# SparkFun_ProtoShield_Kit_rev40.net
KiCad netlist of a schematic drawn in EAGLE
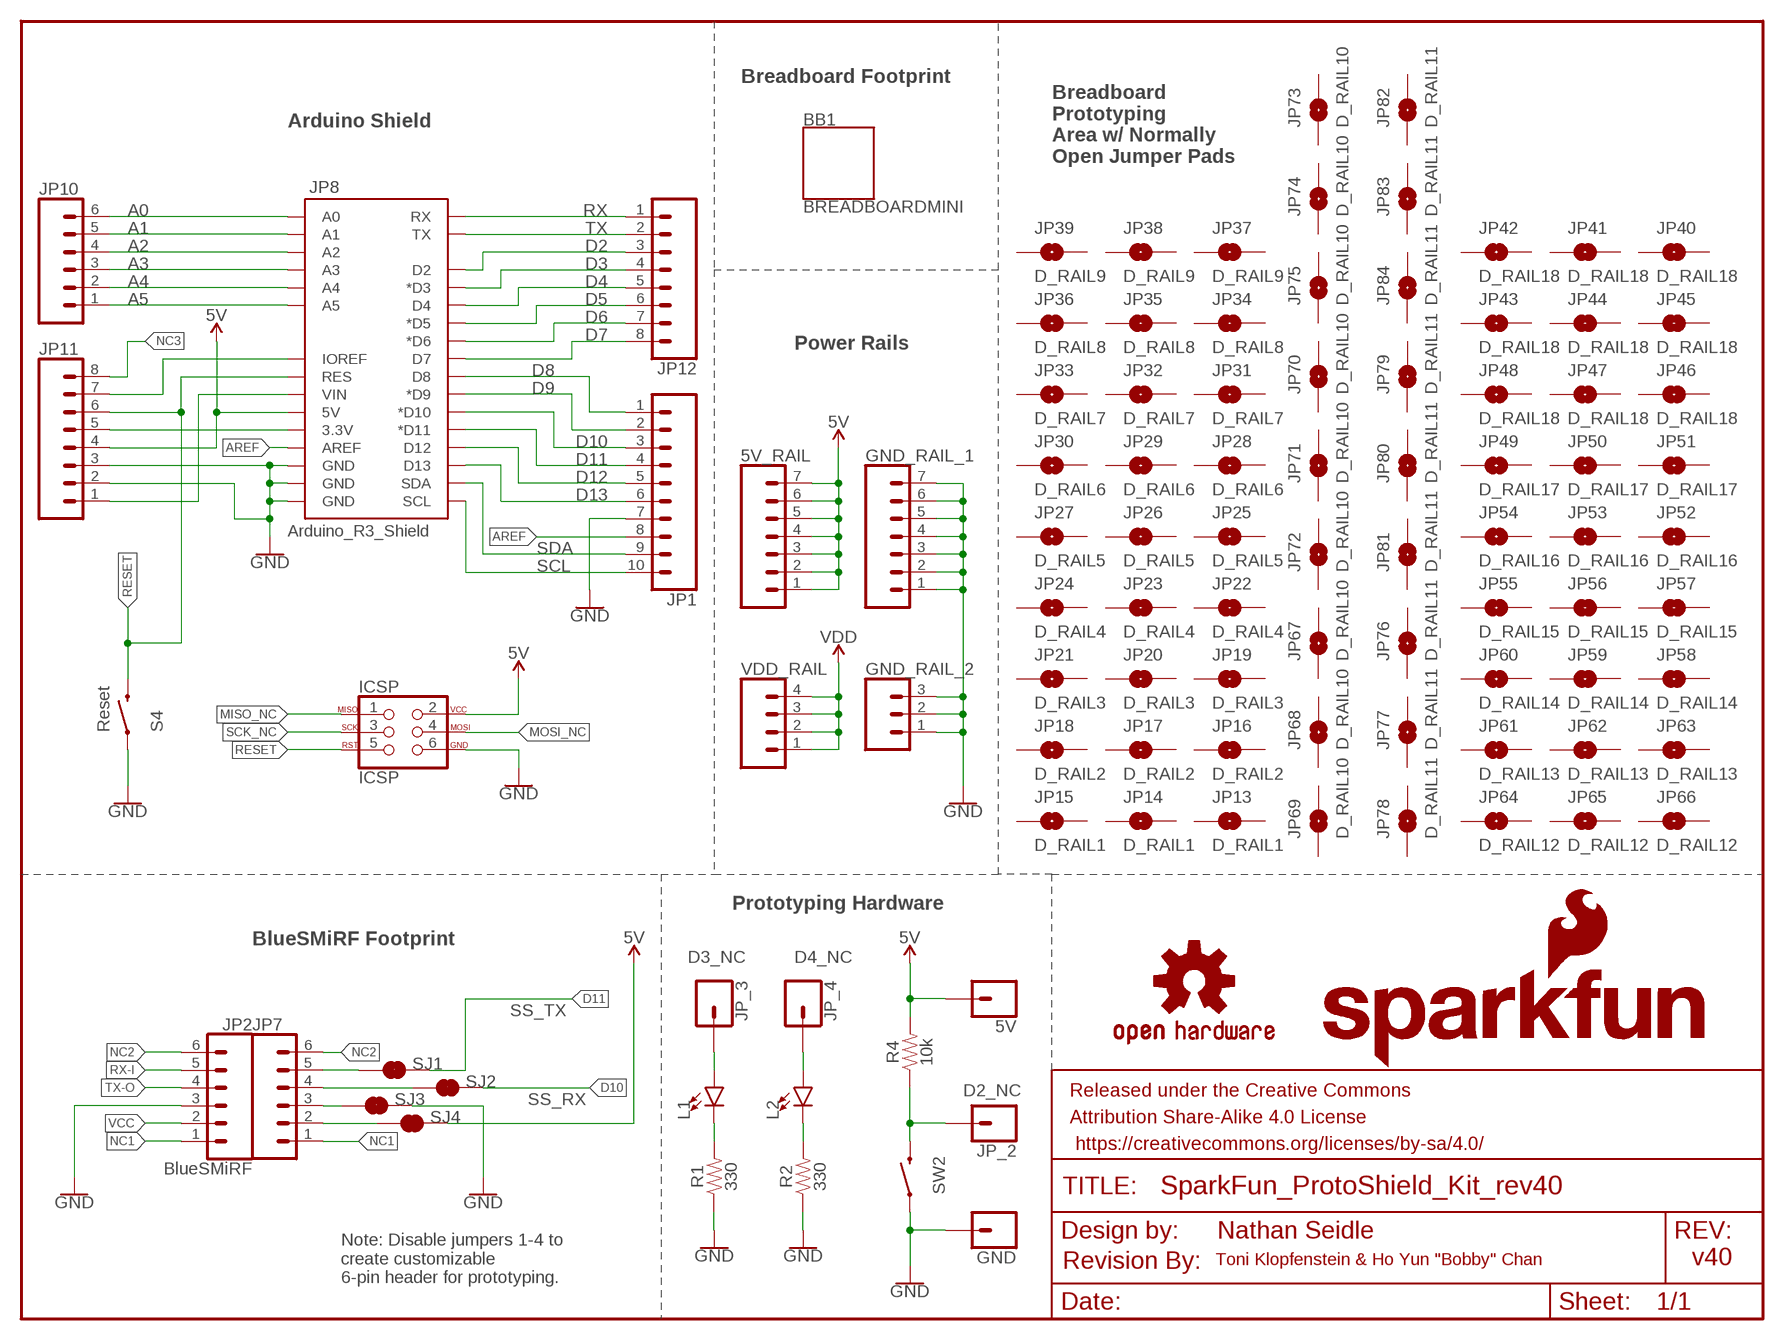
[diagram p0: schematic, sheet 1]

(export (version "E")
  (design (tool "Eeschema 10.0.6"))
  (components
    (comp (ref "5V")
      (value "CONN_01")
      (footprint "eagle-import:1X01")
      (libsource (lib "eagle-import") (part "CONN_01"))
    )
    (comp (ref "5V_RAIL")
      (value "CONN_07NO_SILK")
      (footprint "eagle-import:1X07_NO_SILK")
      (libsource (lib "eagle-import") (part "CONN_07NO_SILK"))
    )
    (comp (ref "BB1")
      (value "BREADBOARDMINI")
      (footprint "eagle-import:BREADBOARD-MINI")
      (libsource (lib "eagle-import") (part "BREADBOARDMINI"))
    )
    (comp (ref "FRAME1")
      (value "FRAME-LETTER")
      (footprint "eagle-import:CREATIVE_COMMONS")
      (libsource (lib "eagle-import") (part "FRAME-LETTER"))
    )
    (comp (ref "GND")
      (value "CONN_01")
      (footprint "eagle-import:1X01")
      (libsource (lib "eagle-import") (part "CONN_01"))
    )
    (comp (ref "GND_RAIL_1")
      (value "CONN_07NO_SILK")
      (footprint "eagle-import:1X07_NO_SILK")
      (libsource (lib "eagle-import") (part "CONN_07NO_SILK"))
    )
    (comp (ref "GND_RAIL_2")
      (value "CONN_031X03_NO_SILK")
      (footprint "eagle-import:1X03_NO_SILK")
      (libsource (lib "eagle-import") (part "CONN_031X03_NO_SILK"))
    )
    (comp (ref "ICSP")
      (value "ICSP")
      (footprint "eagle-import:2X3")
      (libsource (lib "eagle-import") (part "AVR_SPI_PROG_3X2PTH"))
    )
    (comp (ref "JP1")
      (value "CONN_10\"")
      (footprint "eagle-import:1X10")
      (libsource (lib "eagle-import") (part "CONN_10{dblquote}"))
    )
    (comp (ref "JP2")
      (value "BlueSMiRF")
      (footprint "eagle-import:1X06")
      (libsource (lib "eagle-import") (part "CONN_06SILK_FEMALE_PTH"))
    )
    (comp (ref "JP7")
      (value "CONN_06SILK_FEMALE_PTH")
      (footprint "eagle-import:1X06")
      (libsource (lib "eagle-import") (part "CONN_06SILK_FEMALE_PTH"))
    )
    (comp (ref "JP8")
      (value "ARDUINO_R3_SHIELDR3_PROTO_SHIELD")
      (footprint "eagle-import:UNO_R3_PROTO_SHIELD")
      (libsource (lib "eagle-import") (part "ARDUINO_R3_SHIELDR3_PROTO_SHIELD"))
    )
    (comp (ref "JP10")
      (value "CONN_06SILK_FEMALE_PTH")
      (footprint "eagle-import:1X06")
      (libsource (lib "eagle-import") (part "CONN_06SILK_FEMALE_PTH"))
    )
    (comp (ref "JP11")
      (value "CONN_08\"")
      (footprint "eagle-import:1X08")
      (libsource (lib "eagle-import") (part "CONN_08{dblquote}"))
    )
    (comp (ref "JP12")
      (value "CONN_08\"")
      (footprint "eagle-import:1X08")
      (libsource (lib "eagle-import") (part "CONN_08{dblquote}"))
    )
    (comp (ref "JP13")
      (value "D_RAIL1")
      (footprint "eagle-import:SMT-JUMPER_2_NO_NO-SILK")
      (libsource (lib "eagle-import") (part "JUMPER-SMT_2_NO_NO-SILK"))
    )
    (comp (ref "JP14")
      (value "D_RAIL1")
      (footprint "eagle-import:SMT-JUMPER_2_NO_NO-SILK")
      (libsource (lib "eagle-import") (part "JUMPER-SMT_2_NO_NO-SILK"))
    )
    (comp (ref "JP15")
      (value "D_RAIL1")
      (footprint "eagle-import:SMT-JUMPER_2_NO_NO-SILK")
      (libsource (lib "eagle-import") (part "JUMPER-SMT_2_NO_NO-SILK"))
    )
    (comp (ref "JP16")
      (value "D_RAIL2")
      (footprint "eagle-import:SMT-JUMPER_2_NO_NO-SILK")
      (libsource (lib "eagle-import") (part "JUMPER-SMT_2_NO_NO-SILK"))
    )
    (comp (ref "JP17")
      (value "D_RAIL2")
      (footprint "eagle-import:SMT-JUMPER_2_NO_NO-SILK")
      (libsource (lib "eagle-import") (part "JUMPER-SMT_2_NO_NO-SILK"))
    )
    (comp (ref "JP18")
      (value "D_RAIL2")
      (footprint "eagle-import:SMT-JUMPER_2_NO_NO-SILK")
      (libsource (lib "eagle-import") (part "JUMPER-SMT_2_NO_NO-SILK"))
    )
    (comp (ref "JP19")
      (value "D_RAIL3")
      (footprint "eagle-import:SMT-JUMPER_2_NO_NO-SILK")
      (libsource (lib "eagle-import") (part "JUMPER-SMT_2_NO_NO-SILK"))
    )
    (comp (ref "JP20")
      (value "D_RAIL3")
      (footprint "eagle-import:SMT-JUMPER_2_NO_NO-SILK")
      (libsource (lib "eagle-import") (part "JUMPER-SMT_2_NO_NO-SILK"))
    )
    (comp (ref "JP21")
      (value "D_RAIL3")
      (footprint "eagle-import:SMT-JUMPER_2_NO_NO-SILK")
      (libsource (lib "eagle-import") (part "JUMPER-SMT_2_NO_NO-SILK"))
    )
    (comp (ref "JP22")
      (value "D_RAIL4")
      (footprint "eagle-import:SMT-JUMPER_2_NO_NO-SILK")
      (libsource (lib "eagle-import") (part "JUMPER-SMT_2_NO_NO-SILK"))
    )
    (comp (ref "JP23")
      (value "D_RAIL4")
      (footprint "eagle-import:SMT-JUMPER_2_NO_NO-SILK")
      (libsource (lib "eagle-import") (part "JUMPER-SMT_2_NO_NO-SILK"))
    )
    (comp (ref "JP24")
      (value "D_RAIL4")
      (footprint "eagle-import:SMT-JUMPER_2_NO_NO-SILK")
      (libsource (lib "eagle-import") (part "JUMPER-SMT_2_NO_NO-SILK"))
    )
    (comp (ref "JP25")
      (value "D_RAIL5")
      (footprint "eagle-import:SMT-JUMPER_2_NO_NO-SILK")
      (libsource (lib "eagle-import") (part "JUMPER-SMT_2_NO_NO-SILK"))
    )
    (comp (ref "JP26")
      (value "D_RAIL5")
      (footprint "eagle-import:SMT-JUMPER_2_NO_NO-SILK")
      (libsource (lib "eagle-import") (part "JUMPER-SMT_2_NO_NO-SILK"))
    )
    (comp (ref "JP27")
      (value "D_RAIL5")
      (footprint "eagle-import:SMT-JUMPER_2_NO_NO-SILK")
      (libsource (lib "eagle-import") (part "JUMPER-SMT_2_NO_NO-SILK"))
    )
    (comp (ref "JP28")
      (value "D_RAIL6")
      (footprint "eagle-import:SMT-JUMPER_2_NO_NO-SILK")
      (libsource (lib "eagle-import") (part "JUMPER-SMT_2_NO_NO-SILK"))
    )
    (comp (ref "JP29")
      (value "D_RAIL6")
      (footprint "eagle-import:SMT-JUMPER_2_NO_NO-SILK")
      (libsource (lib "eagle-import") (part "JUMPER-SMT_2_NO_NO-SILK"))
    )
    (comp (ref "JP30")
      (value "D_RAIL6")
      (footprint "eagle-import:SMT-JUMPER_2_NO_NO-SILK")
      (libsource (lib "eagle-import") (part "JUMPER-SMT_2_NO_NO-SILK"))
    )
    (comp (ref "JP31")
      (value "D_RAIL7")
      (footprint "eagle-import:SMT-JUMPER_2_NO_NO-SILK")
      (libsource (lib "eagle-import") (part "JUMPER-SMT_2_NO_NO-SILK"))
    )
    (comp (ref "JP32")
      (value "D_RAIL7")
      (footprint "eagle-import:SMT-JUMPER_2_NO_NO-SILK")
      (libsource (lib "eagle-import") (part "JUMPER-SMT_2_NO_NO-SILK"))
    )
    (comp (ref "JP33")
      (value "D_RAIL7")
      (footprint "eagle-import:SMT-JUMPER_2_NO_NO-SILK")
      (libsource (lib "eagle-import") (part "JUMPER-SMT_2_NO_NO-SILK"))
    )
    (comp (ref "JP34")
      (value "D_RAIL8")
      (footprint "eagle-import:SMT-JUMPER_2_NO_NO-SILK")
      (libsource (lib "eagle-import") (part "JUMPER-SMT_2_NO_NO-SILK"))
    )
    (comp (ref "JP35")
      (value "D_RAIL8")
      (footprint "eagle-import:SMT-JUMPER_2_NO_NO-SILK")
      (libsource (lib "eagle-import") (part "JUMPER-SMT_2_NO_NO-SILK"))
    )
    (comp (ref "JP36")
      (value "D_RAIL8")
      (footprint "eagle-import:SMT-JUMPER_2_NO_NO-SILK")
      (libsource (lib "eagle-import") (part "JUMPER-SMT_2_NO_NO-SILK"))
    )
    (comp (ref "JP37")
      (value "D_RAIL9")
      (footprint "eagle-import:SMT-JUMPER_2_NO_NO-SILK")
      (libsource (lib "eagle-import") (part "JUMPER-SMT_2_NO_NO-SILK"))
    )
    (comp (ref "JP38")
      (value "D_RAIL9")
      (footprint "eagle-import:SMT-JUMPER_2_NO_NO-SILK")
      (libsource (lib "eagle-import") (part "JUMPER-SMT_2_NO_NO-SILK"))
    )
    (comp (ref "JP39")
      (value "D_RAIL9")
      (footprint "eagle-import:SMT-JUMPER_2_NO_NO-SILK")
      (libsource (lib "eagle-import") (part "JUMPER-SMT_2_NO_NO-SILK"))
    )
    (comp (ref "JP40")
      (value "D_RAIL18")
      (footprint "eagle-import:SMT-JUMPER_2_NO_NO-SILK")
      (libsource (lib "eagle-import") (part "JUMPER-SMT_2_NO_NO-SILK"))
    )
    (comp (ref "JP41")
      (value "D_RAIL18")
      (footprint "eagle-import:SMT-JUMPER_2_NO_NO-SILK")
      (libsource (lib "eagle-import") (part "JUMPER-SMT_2_NO_NO-SILK"))
    )
    (comp (ref "JP42")
      (value "D_RAIL18")
      (footprint "eagle-import:SMT-JUMPER_2_NO_NO-SILK")
      (libsource (lib "eagle-import") (part "JUMPER-SMT_2_NO_NO-SILK"))
    )
    (comp (ref "JP43")
      (value "D_RAIL18")
      (footprint "eagle-import:SMT-JUMPER_2_NO_NO-SILK")
      (libsource (lib "eagle-import") (part "JUMPER-SMT_2_NO_NO-SILK"))
    )
    (comp (ref "JP44")
      (value "D_RAIL18")
      (footprint "eagle-import:SMT-JUMPER_2_NO_NO-SILK")
      (libsource (lib "eagle-import") (part "JUMPER-SMT_2_NO_NO-SILK"))
    )
    (comp (ref "JP45")
      (value "D_RAIL18")
      (footprint "eagle-import:SMT-JUMPER_2_NO_NO-SILK")
      (libsource (lib "eagle-import") (part "JUMPER-SMT_2_NO_NO-SILK"))
    )
    (comp (ref "JP46")
      (value "D_RAIL18")
      (footprint "eagle-import:SMT-JUMPER_2_NO_NO-SILK")
      (libsource (lib "eagle-import") (part "JUMPER-SMT_2_NO_NO-SILK"))
    )
    (comp (ref "JP47")
      (value "D_RAIL18")
      (footprint "eagle-import:SMT-JUMPER_2_NO_NO-SILK")
      (libsource (lib "eagle-import") (part "JUMPER-SMT_2_NO_NO-SILK"))
    )
    (comp (ref "JP48")
      (value "D_RAIL18")
      (footprint "eagle-import:SMT-JUMPER_2_NO_NO-SILK")
      (libsource (lib "eagle-import") (part "JUMPER-SMT_2_NO_NO-SILK"))
    )
    (comp (ref "JP49")
      (value "D_RAIL17")
      (footprint "eagle-import:SMT-JUMPER_2_NO_NO-SILK")
      (libsource (lib "eagle-import") (part "JUMPER-SMT_2_NO_NO-SILK"))
    )
    (comp (ref "JP50")
      (value "D_RAIL17")
      (footprint "eagle-import:SMT-JUMPER_2_NO_NO-SILK")
      (libsource (lib "eagle-import") (part "JUMPER-SMT_2_NO_NO-SILK"))
    )
    (comp (ref "JP51")
      (value "D_RAIL17")
      (footprint "eagle-import:SMT-JUMPER_2_NO_NO-SILK")
      (libsource (lib "eagle-import") (part "JUMPER-SMT_2_NO_NO-SILK"))
    )
    (comp (ref "JP52")
      (value "D_RAIL16")
      (footprint "eagle-import:SMT-JUMPER_2_NO_NO-SILK")
      (libsource (lib "eagle-import") (part "JUMPER-SMT_2_NO_NO-SILK"))
    )
    (comp (ref "JP53")
      (value "D_RAIL16")
      (footprint "eagle-import:SMT-JUMPER_2_NO_NO-SILK")
      (libsource (lib "eagle-import") (part "JUMPER-SMT_2_NO_NO-SILK"))
    )
    (comp (ref "JP54")
      (value "D_RAIL16")
      (footprint "eagle-import:SMT-JUMPER_2_NO_NO-SILK")
      (libsource (lib "eagle-import") (part "JUMPER-SMT_2_NO_NO-SILK"))
    )
    (comp (ref "JP55")
      (value "D_RAIL15")
      (footprint "eagle-import:SMT-JUMPER_2_NO_NO-SILK")
      (libsource (lib "eagle-import") (part "JUMPER-SMT_2_NO_NO-SILK"))
    )
    (comp (ref "JP56")
      (value "D_RAIL15")
      (footprint "eagle-import:SMT-JUMPER_2_NO_NO-SILK")
      (libsource (lib "eagle-import") (part "JUMPER-SMT_2_NO_NO-SILK"))
    )
    (comp (ref "JP57")
      (value "D_RAIL15")
      (footprint "eagle-import:SMT-JUMPER_2_NO_NO-SILK")
      (libsource (lib "eagle-import") (part "JUMPER-SMT_2_NO_NO-SILK"))
    )
    (comp (ref "JP58")
      (value "D_RAIL14")
      (footprint "eagle-import:SMT-JUMPER_2_NO_NO-SILK")
      (libsource (lib "eagle-import") (part "JUMPER-SMT_2_NO_NO-SILK"))
    )
    (comp (ref "JP59")
      (value "D_RAIL14")
      (footprint "eagle-import:SMT-JUMPER_2_NO_NO-SILK")
      (libsource (lib "eagle-import") (part "JUMPER-SMT_2_NO_NO-SILK"))
    )
    (comp (ref "JP60")
      (value "D_RAIL14")
      (footprint "eagle-import:SMT-JUMPER_2_NO_NO-SILK")
      (libsource (lib "eagle-import") (part "JUMPER-SMT_2_NO_NO-SILK"))
    )
    (comp (ref "JP61")
      (value "D_RAIL13")
      (footprint "eagle-import:SMT-JUMPER_2_NO_NO-SILK")
      (libsource (lib "eagle-import") (part "JUMPER-SMT_2_NO_NO-SILK"))
    )
    (comp (ref "JP62")
      (value "D_RAIL13")
      (footprint "eagle-import:SMT-JUMPER_2_NO_NO-SILK")
      (libsource (lib "eagle-import") (part "JUMPER-SMT_2_NO_NO-SILK"))
    )
    (comp (ref "JP63")
      (value "D_RAIL13")
      (footprint "eagle-import:SMT-JUMPER_2_NO_NO-SILK")
      (libsource (lib "eagle-import") (part "JUMPER-SMT_2_NO_NO-SILK"))
    )
    (comp (ref "JP64")
      (value "D_RAIL12")
      (footprint "eagle-import:SMT-JUMPER_2_NO_NO-SILK")
      (libsource (lib "eagle-import") (part "JUMPER-SMT_2_NO_NO-SILK"))
    )
    (comp (ref "JP65")
      (value "D_RAIL12")
      (footprint "eagle-import:SMT-JUMPER_2_NO_NO-SILK")
      (libsource (lib "eagle-import") (part "JUMPER-SMT_2_NO_NO-SILK"))
    )
    (comp (ref "JP66")
      (value "D_RAIL12")
      (footprint "eagle-import:SMT-JUMPER_2_NO_NO-SILK")
      (libsource (lib "eagle-import") (part "JUMPER-SMT_2_NO_NO-SILK"))
    )
    (comp (ref "JP67")
      (value "D_RAIL10")
      (footprint "eagle-import:SMT-JUMPER_2_NO_NO-SILK")
      (libsource (lib "eagle-import") (part "JUMPER-SMT_2_NO_NO-SILK"))
    )
    (comp (ref "JP68")
      (value "D_RAIL10")
      (footprint "eagle-import:SMT-JUMPER_2_NO_NO-SILK")
      (libsource (lib "eagle-import") (part "JUMPER-SMT_2_NO_NO-SILK"))
    )
    (comp (ref "JP69")
      (value "D_RAIL10")
      (footprint "eagle-import:SMT-JUMPER_2_NO_NO-SILK")
      (libsource (lib "eagle-import") (part "JUMPER-SMT_2_NO_NO-SILK"))
    )
    (comp (ref "JP70")
      (value "D_RAIL10")
      (footprint "eagle-import:SMT-JUMPER_2_NO_NO-SILK")
      (libsource (lib "eagle-import") (part "JUMPER-SMT_2_NO_NO-SILK"))
    )
    (comp (ref "JP71")
      (value "D_RAIL10")
      (footprint "eagle-import:SMT-JUMPER_2_NO_NO-SILK")
      (libsource (lib "eagle-import") (part "JUMPER-SMT_2_NO_NO-SILK"))
    )
    (comp (ref "JP72")
      (value "D_RAIL10")
      (footprint "eagle-import:SMT-JUMPER_2_NO_NO-SILK")
      (libsource (lib "eagle-import") (part "JUMPER-SMT_2_NO_NO-SILK"))
    )
    (comp (ref "JP73")
      (value "D_RAIL10")
      (footprint "eagle-import:SMT-JUMPER_2_NO_NO-SILK")
      (libsource (lib "eagle-import") (part "JUMPER-SMT_2_NO_NO-SILK"))
    )
    (comp (ref "JP74")
      (value "D_RAIL10")
      (footprint "eagle-import:SMT-JUMPER_2_NO_NO-SILK")
      (libsource (lib "eagle-import") (part "JUMPER-SMT_2_NO_NO-SILK"))
    )
    (comp (ref "JP75")
      (value "D_RAIL10")
      (footprint "eagle-import:SMT-JUMPER_2_NO_NO-SILK")
      (libsource (lib "eagle-import") (part "JUMPER-SMT_2_NO_NO-SILK"))
    )
    (comp (ref "JP76")
      (value "D_RAIL11")
      (footprint "eagle-import:SMT-JUMPER_2_NO_NO-SILK")
      (libsource (lib "eagle-import") (part "JUMPER-SMT_2_NO_NO-SILK"))
    )
    (comp (ref "JP77")
      (value "D_RAIL11")
      (footprint "eagle-import:SMT-JUMPER_2_NO_NO-SILK")
      (libsource (lib "eagle-import") (part "JUMPER-SMT_2_NO_NO-SILK"))
    )
    (comp (ref "JP78")
      (value "D_RAIL11")
      (footprint "eagle-import:SMT-JUMPER_2_NO_NO-SILK")
      (libsource (lib "eagle-import") (part "JUMPER-SMT_2_NO_NO-SILK"))
    )
    (comp (ref "JP79")
      (value "D_RAIL11")
      (footprint "eagle-import:SMT-JUMPER_2_NO_NO-SILK")
      (libsource (lib "eagle-import") (part "JUMPER-SMT_2_NO_NO-SILK"))
    )
    (comp (ref "JP80")
      (value "D_RAIL11")
      (footprint "eagle-import:SMT-JUMPER_2_NO_NO-SILK")
      (libsource (lib "eagle-import") (part "JUMPER-SMT_2_NO_NO-SILK"))
    )
    (comp (ref "JP81")
      (value "D_RAIL11")
      (footprint "eagle-import:SMT-JUMPER_2_NO_NO-SILK")
      (libsource (lib "eagle-import") (part "JUMPER-SMT_2_NO_NO-SILK"))
    )
    (comp (ref "JP82")
      (value "D_RAIL11")
      (footprint "eagle-import:SMT-JUMPER_2_NO_NO-SILK")
      (libsource (lib "eagle-import") (part "JUMPER-SMT_2_NO_NO-SILK"))
    )
    (comp (ref "JP83")
      (value "D_RAIL11")
      (footprint "eagle-import:SMT-JUMPER_2_NO_NO-SILK")
      (libsource (lib "eagle-import") (part "JUMPER-SMT_2_NO_NO-SILK"))
    )
    (comp (ref "JP84")
      (value "D_RAIL11")
      (footprint "eagle-import:SMT-JUMPER_2_NO_NO-SILK")
      (libsource (lib "eagle-import") (part "JUMPER-SMT_2_NO_NO-SILK"))
    )
    (comp (ref "JP_2")
      (value "CONN_01")
      (footprint "eagle-import:1X01")
      (libsource (lib "eagle-import") (part "CONN_01"))
    )
    (comp (ref "JP_3")
      (value "CONN_01")
      (footprint "eagle-import:1X01")
      (libsource (lib "eagle-import") (part "CONN_01"))
    )
    (comp (ref "JP_4")
      (value "CONN_01")
      (footprint "eagle-import:1X01")
      (libsource (lib "eagle-import") (part "CONN_01"))
    )
    (comp (ref "L1")
      (value "LED3MM")
      (footprint "eagle-import:LED_3MM")
      (libsource (lib "eagle-import") (part "LED3MM"))
    )
    (comp (ref "L2")
      (value "LED3MM")
      (footprint "eagle-import:LED_3MM")
      (libsource (lib "eagle-import") (part "LED3MM"))
    )
    (comp (ref "LOGO1")
      (value "OSHW-LOGOS")
      (footprint "eagle-import:OSHW-LOGO-S")
      (libsource (lib "eagle-import") (part "OSHW-LOGOS"))
    )
    (comp (ref "R1")
      (value "330")
      (footprint "eagle-import:AXIAL-0.3")
      (libsource (lib "eagle-import") (part "330OHM-HORIZ-1/10W-5%"))
    )
    (comp (ref "R2")
      (value "330")
      (footprint "eagle-import:AXIAL-0.3")
      (libsource (lib "eagle-import") (part "330OHM-HORIZ-1/10W-5%"))
    )
    (comp (ref "R4")
      (value "10k")
      (footprint "eagle-import:AXIAL-0.3")
      (libsource (lib "eagle-import") (part "10KOHM-HORIZ-1/4W-5%"))
    )
    (comp (ref "S4")
      (value "MOMENTARY-SWITCH-SPST-PTH-6.0MM")
      (footprint "eagle-import:TACTILE_SWITCH_PTH_6.0MM")
      (libsource (lib "eagle-import") (part "MOMENTARY-SWITCH-SPST-PTH-6.0MM"))
    )
    (comp (ref "SJ1")
      (value "JUMPER-SMT_2_NC_TRACE_SILK")
      (footprint "eagle-import:SMT-JUMPER_2_NC_TRACE_SILK")
      (libsource (lib "eagle-import") (part "JUMPER-SMT_2_NC_TRACE_SILK"))
    )
    (comp (ref "SJ2")
      (value "JUMPER-SMT_2_NC_TRACE_SILK")
      (footprint "eagle-import:SMT-JUMPER_2_NC_TRACE_SILK")
      (libsource (lib "eagle-import") (part "JUMPER-SMT_2_NC_TRACE_SILK"))
    )
    (comp (ref "SJ3")
      (value "JUMPER-SMT_2_NC_TRACE_SILK")
      (footprint "eagle-import:SMT-JUMPER_2_NC_TRACE_SILK")
      (libsource (lib "eagle-import") (part "JUMPER-SMT_2_NC_TRACE_SILK"))
    )
    (comp (ref "SJ4")
      (value "JUMPER-SMT_2_NC_TRACE_SILK")
      (footprint "eagle-import:SMT-JUMPER_2_NC_TRACE_SILK")
      (libsource (lib "eagle-import") (part "JUMPER-SMT_2_NC_TRACE_SILK"))
    )
    (comp (ref "SW2")
      (value "MOMENTARY-SWITCH-SPST-PTH-6.0MM")
      (footprint "eagle-import:TACTILE_SWITCH_PTH_6.0MM")
      (libsource (lib "eagle-import") (part "MOMENTARY-SWITCH-SPST-PTH-6.0MM"))
    )
    (comp (ref "U$1")
      (value "SFE_LOGO_NAME_FLAME.1_INCH")
      (footprint "eagle-import:SFE_LOGO_NAME_FLAME_.1")
      (libsource (lib "eagle-import") (part "SFE_LOGO_NAME_FLAME.1_INCH"))
    )
    (comp (ref "U$2")
      (value "REVISION")
      (footprint "eagle-import:REVISION")
      (libsource (lib "eagle-import") (part "REVISION"))
    )
    (comp (ref "VDD_RAIL")
      (value "CONN_041X04_NO_SILK")
      (footprint "eagle-import:1X04_NO_SILK")
      (libsource (lib "eagle-import") (part "CONN_041X04_NO_SILK"))
    )
  )
  (nets
    (net (code "1") (name "/D2") (class "Default")
      (node (ref "JP12") (pin "3") (pinfunction "3_3") (pintype "passive"))
      (node (ref "JP8") (pin "D2") (pinfunction "D2_D2") (pintype "bidirectional"))
    )
    (net (code "2") (name "/D2_NC") (class "Default")
      (node (ref "JP_2") (pin "1") (pinfunction "1_1") (pintype "passive"))
      (node (ref "R4") (pin "P$1") (pinfunction "1_P$1") (pintype "passive"))
      (node (ref "SW2") (pin "3") (pinfunction "2_3") (pintype "passive"))
    )
    (net (code "3") (name "/D3") (class "Default")
      (node (ref "JP12") (pin "4") (pinfunction "4_4") (pintype "passive"))
      (node (ref "JP8") (pin "D3") (pinfunction "*D3_D3") (pintype "bidirectional"))
    )
    (net (code "4") (name "/D4") (class "Default")
      (node (ref "JP12") (pin "5") (pinfunction "5_5") (pintype "passive"))
      (node (ref "JP8") (pin "D4") (pinfunction "D4_D4") (pintype "bidirectional"))
    )
    (net (code "5") (name "/D5") (class "Default")
      (node (ref "JP12") (pin "6") (pinfunction "6_6") (pintype "passive"))
      (node (ref "JP8") (pin "D5") (pinfunction "*D5_D5") (pintype "bidirectional"))
    )
    (net (code "6") (name "/D6") (class "Default")
      (node (ref "JP12") (pin "7") (pinfunction "7_7") (pintype "passive"))
      (node (ref "JP8") (pin "D6") (pinfunction "*D6_D6") (pintype "bidirectional"))
    )
    (net (code "7") (name "/D7") (class "Default")
      (node (ref "JP12") (pin "8") (pinfunction "8_8") (pintype "passive"))
      (node (ref "JP8") (pin "D7") (pinfunction "D7_D7") (pintype "bidirectional"))
    )
    (net (code "8") (name "/D8") (class "Default")
      (node (ref "JP1") (pin "1") (pinfunction "1_1") (pintype "passive"))
      (node (ref "JP8") (pin "D8") (pinfunction "D8_D8") (pintype "bidirectional"))
    )
    (net (code "9") (name "/D9") (class "Default")
      (node (ref "JP1") (pin "2") (pinfunction "2_2") (pintype "passive"))
      (node (ref "JP8") (pin "D9") (pinfunction "*D9_D9") (pintype "bidirectional"))
    )
    (net (code "10") (name "/D12") (class "Default")
      (node (ref "JP1") (pin "5") (pinfunction "5_5") (pintype "passive"))
      (node (ref "JP8") (pin "D12") (pinfunction "D12_D12") (pintype "bidirectional"))
    )
    (net (code "11") (name "/D13") (class "Default")
      (node (ref "JP1") (pin "6") (pinfunction "6_6") (pintype "passive"))
      (node (ref "JP8") (pin "D13") (pinfunction "D13_D13") (pintype "bidirectional"))
    )
    (net (code "12") (name "/RX") (class "Default")
      (node (ref "JP12") (pin "1") (pinfunction "1_1") (pintype "passive"))
      (node (ref "JP8") (pin "RX") (pinfunction "RX_RX") (pintype "bidirectional"))
    )
    (net (code "13") (name "/SCL") (class "Default")
      (node (ref "JP1") (pin "10") (pinfunction "10_10") (pintype "passive"))
      (node (ref "JP8") (pin "SCL") (pinfunction "SCL_SCL") (pintype "bidirectional"))
    )
    (net (code "14") (name "/SDA") (class "Default")
      (node (ref "JP1") (pin "9") (pinfunction "9_9") (pintype "passive"))
      (node (ref "JP8") (pin "SDA") (pinfunction "SDA_SDA") (pintype "bidirectional"))
    )
    (net (code "15") (name "/TX") (class "Default")
      (node (ref "JP12") (pin "2") (pinfunction "2_2") (pintype "passive"))
      (node (ref "JP8") (pin "TX") (pinfunction "TX_TX") (pintype "bidirectional"))
    )
    (net (code "16") (name "5V") (class "Default")
      (node (ref "5V") (pin "1") (pinfunction "1_1") (pintype "passive"))
      (node (ref "5V_RAIL") (pin "1") (pinfunction "1_1") (pintype "passive"))
      (node (ref "5V_RAIL") (pin "2") (pinfunction "2_2") (pintype "passive"))
      (node (ref "5V_RAIL") (pin "3") (pinfunction "3_3") (pintype "passive"))
      (node (ref "5V_RAIL") (pin "4") (pinfunction "4_4") (pintype "passive"))
      (node (ref "5V_RAIL") (pin "5") (pinfunction "5_5") (pintype "passive"))
      (node (ref "5V_RAIL") (pin "6") (pinfunction "6_6") (pintype "passive"))
      (node (ref "5V_RAIL") (pin "7") (pinfunction "7_7") (pintype "passive"))
      (node (ref "ICSP") (pin "2") (pinfunction "2_2") (pintype "passive"))
      (node (ref "JP11") (pin "4") (pinfunction "4_4") (pintype "passive"))
      (node (ref "JP8") (pin "5V") (pinfunction "5V_5V") (pintype "bidirectional"))
      (node (ref "R4") (pin "P$2") (pinfunction "2_P$2") (pintype "passive"))
      (node (ref "SJ4") (pin "2") (pinfunction "2_2") (pintype "passive"))
    )
    (net (code "17") (name "AREF") (class "Default")
      (node (ref "JP1") (pin "8") (pinfunction "8_8") (pintype "passive"))
      (node (ref "JP8") (pin "AREF") (pinfunction "AREF_AREF") (pintype "bidirectional"))
    )
    (net (code "18") (name "D10") (class "Default")
      (node (ref "JP1") (pin "3") (pinfunction "3_3") (pintype "passive"))
      (node (ref "JP8") (pin "D10") (pinfunction "*D10_D10") (pintype "bidirectional"))
      (node (ref "SJ2") (pin "2") (pinfunction "2_2") (pintype "passive"))
    )
    (net (code "19") (name "D11") (class "Default")
      (node (ref "JP1") (pin "4") (pinfunction "4_4") (pintype "passive"))
      (node (ref "JP8") (pin "D11") (pinfunction "*D11_D11") (pintype "bidirectional"))
      (node (ref "SJ1") (pin "2") (pinfunction "2_2") (pintype "passive"))
    )
    (net (code "20") (name "GND") (class "Default")
      (node (ref "GND") (pin "1") (pinfunction "1_1") (pintype "passive"))
      (node (ref "GND_RAIL_1") (pin "1") (pinfunction "1_1") (pintype "passive"))
      (node (ref "GND_RAIL_1") (pin "2") (pinfunction "2_2") (pintype "passive"))
      (node (ref "GND_RAIL_1") (pin "3") (pinfunction "3_3") (pintype "passive"))
      (node (ref "GND_RAIL_1") (pin "4") (pinfunction "4_4") (pintype "passive"))
      (node (ref "GND_RAIL_1") (pin "5") (pinfunction "5_5") (pintype "passive"))
      (node (ref "GND_RAIL_1") (pin "6") (pinfunction "6_6") (pintype "passive"))
      (node (ref "GND_RAIL_1") (pin "7") (pinfunction "7_7") (pintype "passive"))
      (node (ref "GND_RAIL_2") (pin "1") (pinfunction "1_1") (pintype "passive"))
      (node (ref "GND_RAIL_2") (pin "2") (pinfunction "2_2") (pintype "passive"))
      (node (ref "GND_RAIL_2") (pin "3") (pinfunction "3_3") (pintype "passive"))
      (node (ref "ICSP") (pin "6") (pinfunction "6_6") (pintype "passive"))
      (node (ref "JP1") (pin "7") (pinfunction "7_7") (pintype "passive"))
      (node (ref "JP11") (pin "2") (pinfunction "2_2") (pintype "passive"))
      (node (ref "JP11") (pin "3") (pinfunction "3_3") (pintype "passive"))
      (node (ref "JP2") (pin "3") (pinfunction "3_3") (pintype "passive"))
      (node (ref "JP7") (pin "3") (pinfunction "3_3") (pintype "passive"))
      (node (ref "JP8") (pin "GND@0") (pinfunction "GND_GND@0") (pintype "bidirectional"))
      (node (ref "JP8") (pin "GND@1") (pinfunction "GND_GND@1") (pintype "bidirectional"))
      (node (ref "JP8") (pin "GND@2") (pinfunction "GND_GND@2") (pintype "bidirectional"))
      (node (ref "R1") (pin "P$1") (pinfunction "1_P$1") (pintype "passive"))
      (node (ref "R2") (pin "P$1") (pinfunction "1_P$1") (pintype "passive"))
      (node (ref "S4") (pin "1") (pinfunction "1_1") (pintype "passive"))
      (node (ref "SJ3") (pin "1") (pinfunction "1_1") (pintype "passive"))
      (node (ref "SJ3") (pin "2") (pinfunction "2_2") (pintype "passive"))
      (node (ref "SW2") (pin "1") (pinfunction "1_1") (pintype "passive"))
    )
    (net (code "21") (name "MISO_NC") (class "Default")
      (node (ref "ICSP") (pin "1") (pinfunction "1_1") (pintype "passive"))
    )
    (net (code "22") (name "MOSI_NC") (class "Default")
      (node (ref "ICSP") (pin "4") (pinfunction "4_4") (pintype "passive"))
    )
    (net (code "23") (name "NC1") (class "Default")
      (node (ref "JP2") (pin "1") (pinfunction "1_1") (pintype "passive"))
      (node (ref "JP7") (pin "1") (pinfunction "1_1") (pintype "passive"))
    )
    (net (code "24") (name "NC2") (class "Default")
      (node (ref "JP2") (pin "6") (pinfunction "6_6") (pintype "passive"))
      (node (ref "JP7") (pin "6") (pinfunction "6_6") (pintype "passive"))
    )
    (net (code "25") (name "NC3") (class "Default")
      (node (ref "JP11") (pin "8") (pinfunction "8_8") (pintype "passive"))
    )
    (net (code "26") (name "Net-(JP10-Pad1)") (class "Default")
      (node (ref "JP10") (pin "1") (pinfunction "1_1") (pintype "passive"))
      (node (ref "JP8") (pin "A5") (pinfunction "A5_A5") (pintype "bidirectional"))
    )
    (net (code "27") (name "Net-(JP10-Pad2)") (class "Default")
      (node (ref "JP10") (pin "2") (pinfunction "2_2") (pintype "passive"))
      (node (ref "JP8") (pin "A4") (pinfunction "A4_A4") (pintype "bidirectional"))
    )
    (net (code "28") (name "Net-(JP10-Pad3)") (class "Default")
      (node (ref "JP10") (pin "3") (pinfunction "3_3") (pintype "passive"))
      (node (ref "JP8") (pin "A3") (pinfunction "A3_A3") (pintype "bidirectional"))
    )
    (net (code "29") (name "Net-(JP10-Pad4)") (class "Default")
      (node (ref "JP10") (pin "4") (pinfunction "4_4") (pintype "passive"))
      (node (ref "JP8") (pin "A2") (pinfunction "A2_A2") (pintype "bidirectional"))
    )
    (net (code "30") (name "Net-(JP10-Pad5)") (class "Default")
      (node (ref "JP10") (pin "5") (pinfunction "5_5") (pintype "passive"))
      (node (ref "JP8") (pin "A1") (pinfunction "A1_A1") (pintype "bidirectional"))
    )
    (net (code "31") (name "Net-(JP10-Pad6)") (class "Default")
      (node (ref "JP10") (pin "6") (pinfunction "6_6") (pintype "passive"))
      (node (ref "JP8") (pin "A0") (pinfunction "A0_A0") (pintype "bidirectional"))
    )
    (net (code "32") (name "Net-(JP11-Pad1)") (class "Default")
      (node (ref "JP11") (pin "1") (pinfunction "1_1") (pintype "passive"))
      (node (ref "JP8") (pin "VIN") (pinfunction "VIN_VIN") (pintype "bidirectional"))
    )
    (net (code "33") (name "Net-(JP11-Pad5)") (class "Default")
      (node (ref "JP11") (pin "5") (pinfunction "5_5") (pintype "passive"))
      (node (ref "JP8") (pin "3.3V") (pinfunction "3.3V_3.3V") (pintype "bidirectional"))
    )
    (net (code "34") (name "Net-(JP11-Pad7)") (class "Default")
      (node (ref "JP11") (pin "7") (pinfunction "7_7") (pintype "passive"))
      (node (ref "JP8") (pin "IOREF") (pinfunction "IOREF_IOREF") (pintype "bidirectional"))
    )
    (net (code "35") (name "Net-(JP_3-Pad1)") (class "Default")
      (node (ref "JP_3") (pin "1") (pinfunction "1_1") (pintype "passive"))
      (node (ref "L1") (pin "A") (pinfunction "A_A") (pintype "passive"))
    )
    (net (code "36") (name "Net-(JP_4-Pad1)") (class "Default")
      (node (ref "JP_4") (pin "1") (pinfunction "1_1") (pintype "passive"))
      (node (ref "L2") (pin "A") (pinfunction "A_A") (pintype "passive"))
    )
    (net (code "37") (name "Net-(L1-C)") (class "Default")
      (node (ref "L1") (pin "K") (pinfunction "C_K") (pintype "passive"))
      (node (ref "R1") (pin "P$2") (pinfunction "2_P$2") (pintype "passive"))
    )
    (net (code "38") (name "Net-(L2-C)") (class "Default")
      (node (ref "L2") (pin "K") (pinfunction "C_K") (pintype "passive"))
      (node (ref "R2") (pin "P$2") (pinfunction "2_P$2") (pintype "passive"))
    )
    (net (code "39") (name "RESET") (class "Default")
      (node (ref "ICSP") (pin "5") (pinfunction "5_5") (pintype "passive"))
      (node (ref "JP11") (pin "6") (pinfunction "6_6") (pintype "passive"))
      (node (ref "JP8") (pin "RES") (pinfunction "RES_RES") (pintype "bidirectional"))
      (node (ref "S4") (pin "3") (pinfunction "2_3") (pintype "passive"))
    )
    (net (code "40") (name "RX-I") (class "Default")
      (node (ref "JP2") (pin "5") (pinfunction "5_5") (pintype "passive"))
      (node (ref "JP7") (pin "5") (pinfunction "5_5") (pintype "passive"))
      (node (ref "SJ1") (pin "1") (pinfunction "1_1") (pintype "passive"))
    )
    (net (code "41") (name "SCK_NC") (class "Default")
      (node (ref "ICSP") (pin "3") (pinfunction "3_3") (pintype "passive"))
    )
    (net (code "42") (name "TX-O") (class "Default")
      (node (ref "JP2") (pin "4") (pinfunction "4_4") (pintype "passive"))
      (node (ref "JP7") (pin "4") (pinfunction "4_4") (pintype "passive"))
      (node (ref "SJ2") (pin "1") (pinfunction "1_1") (pintype "passive"))
    )
    (net (code "43") (name "VCC") (class "Default")
      (node (ref "JP2") (pin "2") (pinfunction "2_2") (pintype "passive"))
      (node (ref "JP7") (pin "2") (pinfunction "2_2") (pintype "passive"))
      (node (ref "SJ4") (pin "1") (pinfunction "1_1") (pintype "passive"))
    )
    (net (code "44") (name "VDD") (class "Default")
      (node (ref "VDD_RAIL") (pin "1") (pinfunction "1_1") (pintype "passive"))
      (node (ref "VDD_RAIL") (pin "2") (pinfunction "2_2") (pintype "passive"))
      (node (ref "VDD_RAIL") (pin "3") (pinfunction "3_3") (pintype "passive"))
      (node (ref "VDD_RAIL") (pin "4") (pinfunction "4_4") (pintype "passive"))
    )
    (net (code "45") (name "unconnected-(JP13-Pad1)") (class "Default")
      (node (ref "JP13") (pin "1") (pinfunction "1_1") (pintype "passive"))
    )
    (net (code "46") (name "unconnected-(JP13-Pad2)") (class "Default")
      (node (ref "JP13") (pin "2") (pinfunction "2_2") (pintype "passive"))
    )
    (net (code "47") (name "unconnected-(JP14-Pad1)") (class "Default")
      (node (ref "JP14") (pin "1") (pinfunction "1_1") (pintype "passive"))
    )
    (net (code "48") (name "unconnected-(JP14-Pad2)") (class "Default")
      (node (ref "JP14") (pin "2") (pinfunction "2_2") (pintype "passive"))
    )
    (net (code "49") (name "unconnected-(JP15-Pad1)") (class "Default")
      (node (ref "JP15") (pin "1") (pinfunction "1_1") (pintype "passive"))
    )
    (net (code "50") (name "unconnected-(JP15-Pad2)") (class "Default")
      (node (ref "JP15") (pin "2") (pinfunction "2_2") (pintype "passive"))
    )
    (net (code "51") (name "unconnected-(JP16-Pad1)") (class "Default")
      (node (ref "JP16") (pin "1") (pinfunction "1_1") (pintype "passive"))
    )
    (net (code "52") (name "unconnected-(JP16-Pad2)") (class "Default")
      (node (ref "JP16") (pin "2") (pinfunction "2_2") (pintype "passive"))
    )
    (net (code "53") (name "unconnected-(JP17-Pad1)") (class "Default")
      (node (ref "JP17") (pin "1") (pinfunction "1_1") (pintype "passive"))
    )
    (net (code "54") (name "unconnected-(JP17-Pad2)") (class "Default")
      (node (ref "JP17") (pin "2") (pinfunction "2_2") (pintype "passive"))
    )
    (net (code "55") (name "unconnected-(JP18-Pad1)") (class "Default")
      (node (ref "JP18") (pin "1") (pinfunction "1_1") (pintype "passive"))
    )
    (net (code "56") (name "unconnected-(JP18-Pad2)") (class "Default")
      (node (ref "JP18") (pin "2") (pinfunction "2_2") (pintype "passive"))
    )
    (net (code "57") (name "unconnected-(JP19-Pad1)") (class "Default")
      (node (ref "JP19") (pin "1") (pinfunction "1_1") (pintype "passive"))
    )
    (net (code "58") (name "unconnected-(JP19-Pad2)") (class "Default")
      (node (ref "JP19") (pin "2") (pinfunction "2_2") (pintype "passive"))
    )
    (net (code "59") (name "unconnected-(JP20-Pad1)") (class "Default")
      (node (ref "JP20") (pin "1") (pinfunction "1_1") (pintype "passive"))
    )
    (net (code "60") (name "unconnected-(JP20-Pad2)") (class "Default")
      (node (ref "JP20") (pin "2") (pinfunction "2_2") (pintype "passive"))
    )
    (net (code "61") (name "unconnected-(JP21-Pad1)") (class "Default")
      (node (ref "JP21") (pin "1") (pinfunction "1_1") (pintype "passive"))
    )
    (net (code "62") (name "unconnected-(JP21-Pad2)") (class "Default")
      (node (ref "JP21") (pin "2") (pinfunction "2_2") (pintype "passive"))
    )
    (net (code "63") (name "unconnected-(JP22-Pad1)") (class "Default")
      (node (ref "JP22") (pin "1") (pinfunction "1_1") (pintype "passive"))
    )
    (net (code "64") (name "unconnected-(JP22-Pad2)") (class "Default")
      (node (ref "JP22") (pin "2") (pinfunction "2_2") (pintype "passive"))
    )
    (net (code "65") (name "unconnected-(JP23-Pad1)") (class "Default")
      (node (ref "JP23") (pin "1") (pinfunction "1_1") (pintype "passive"))
    )
    (net (code "66") (name "unconnected-(JP23-Pad2)") (class "Default")
      (node (ref "JP23") (pin "2") (pinfunction "2_2") (pintype "passive"))
    )
    (net (code "67") (name "unconnected-(JP24-Pad1)") (class "Default")
      (node (ref "JP24") (pin "1") (pinfunction "1_1") (pintype "passive"))
    )
    (net (code "68") (name "unconnected-(JP24-Pad2)") (class "Default")
      (node (ref "JP24") (pin "2") (pinfunction "2_2") (pintype "passive"))
    )
    (net (code "69") (name "unconnected-(JP25-Pad1)") (class "Default")
      (node (ref "JP25") (pin "1") (pinfunction "1_1") (pintype "passive"))
    )
    (net (code "70") (name "unconnected-(JP25-Pad2)") (class "Default")
      (node (ref "JP25") (pin "2") (pinfunction "2_2") (pintype "passive"))
    )
    (net (code "71") (name "unconnected-(JP26-Pad1)") (class "Default")
      (node (ref "JP26") (pin "1") (pinfunction "1_1") (pintype "passive"))
    )
    (net (code "72") (name "unconnected-(JP26-Pad2)") (class "Default")
      (node (ref "JP26") (pin "2") (pinfunction "2_2") (pintype "passive"))
    )
    (net (code "73") (name "unconnected-(JP27-Pad1)") (class "Default")
      (node (ref "JP27") (pin "1") (pinfunction "1_1") (pintype "passive"))
    )
    (net (code "74") (name "unconnected-(JP27-Pad2)") (class "Default")
      (node (ref "JP27") (pin "2") (pinfunction "2_2") (pintype "passive"))
    )
    (net (code "75") (name "unconnected-(JP28-Pad1)") (class "Default")
      (node (ref "JP28") (pin "1") (pinfunction "1_1") (pintype "passive"))
    )
    (net (code "76") (name "unconnected-(JP28-Pad2)") (class "Default")
      (node (ref "JP28") (pin "2") (pinfunction "2_2") (pintype "passive"))
    )
    (net (code "77") (name "unconnected-(JP29-Pad1)") (class "Default")
      (node (ref "JP29") (pin "1") (pinfunction "1_1") (pintype "passive"))
    )
    (net (code "78") (name "unconnected-(JP29-Pad2)") (class "Default")
      (node (ref "JP29") (pin "2") (pinfunction "2_2") (pintype "passive"))
    )
    (net (code "79") (name "unconnected-(JP30-Pad1)") (class "Default")
      (node (ref "JP30") (pin "1") (pinfunction "1_1") (pintype "passive"))
    )
    (net (code "80") (name "unconnected-(JP30-Pad2)") (class "Default")
      (node (ref "JP30") (pin "2") (pinfunction "2_2") (pintype "passive"))
    )
    (net (code "81") (name "unconnected-(JP31-Pad1)") (class "Default")
      (node (ref "JP31") (pin "1") (pinfunction "1_1") (pintype "passive"))
    )
    (net (code "82") (name "unconnected-(JP31-Pad2)") (class "Default")
      (node (ref "JP31") (pin "2") (pinfunction "2_2") (pintype "passive"))
    )
    (net (code "83") (name "unconnected-(JP32-Pad1)") (class "Default")
      (node (ref "JP32") (pin "1") (pinfunction "1_1") (pintype "passive"))
    )
    (net (code "84") (name "unconnected-(JP32-Pad2)") (class "Default")
      (node (ref "JP32") (pin "2") (pinfunction "2_2") (pintype "passive"))
    )
    (net (code "85") (name "unconnected-(JP33-Pad1)") (class "Default")
      (node (ref "JP33") (pin "1") (pinfunction "1_1") (pintype "passive"))
    )
    (net (code "86") (name "unconnected-(JP33-Pad2)") (class "Default")
      (node (ref "JP33") (pin "2") (pinfunction "2_2") (pintype "passive"))
    )
    (net (code "87") (name "unconnected-(JP34-Pad1)") (class "Default")
      (node (ref "JP34") (pin "1") (pinfunction "1_1") (pintype "passive"))
    )
    (net (code "88") (name "unconnected-(JP34-Pad2)") (class "Default")
      (node (ref "JP34") (pin "2") (pinfunction "2_2") (pintype "passive"))
    )
    (net (code "89") (name "unconnected-(JP35-Pad1)") (class "Default")
      (node (ref "JP35") (pin "1") (pinfunction "1_1") (pintype "passive"))
    )
    (net (code "90") (name "unconnected-(JP35-Pad2)") (class "Default")
      (node (ref "JP35") (pin "2") (pinfunction "2_2") (pintype "passive"))
    )
    (net (code "91") (name "unconnected-(JP36-Pad1)") (class "Default")
      (node (ref "JP36") (pin "1") (pinfunction "1_1") (pintype "passive"))
    )
    (net (code "92") (name "unconnected-(JP36-Pad2)") (class "Default")
      (node (ref "JP36") (pin "2") (pinfunction "2_2") (pintype "passive"))
    )
    (net (code "93") (name "unconnected-(JP37-Pad1)") (class "Default")
      (node (ref "JP37") (pin "1") (pinfunction "1_1") (pintype "passive"))
    )
    (net (code "94") (name "unconnected-(JP37-Pad2)") (class "Default")
      (node (ref "JP37") (pin "2") (pinfunction "2_2") (pintype "passive"))
    )
    (net (code "95") (name "unconnected-(JP38-Pad1)") (class "Default")
      (node (ref "JP38") (pin "1") (pinfunction "1_1") (pintype "passive"))
    )
    (net (code "96") (name "unconnected-(JP38-Pad2)") (class "Default")
      (node (ref "JP38") (pin "2") (pinfunction "2_2") (pintype "passive"))
    )
    (net (code "97") (name "unconnected-(JP39-Pad1)") (class "Default")
      (node (ref "JP39") (pin "1") (pinfunction "1_1") (pintype "passive"))
    )
    (net (code "98") (name "unconnected-(JP39-Pad2)") (class "Default")
      (node (ref "JP39") (pin "2") (pinfunction "2_2") (pintype "passive"))
    )
    (net (code "99") (name "unconnected-(JP40-Pad1)") (class "Default")
      (node (ref "JP40") (pin "1") (pinfunction "1_1") (pintype "passive"))
    )
    (net (code "100") (name "unconnected-(JP40-Pad2)") (class "Default")
      (node (ref "JP40") (pin "2") (pinfunction "2_2") (pintype "passive"))
    )
    (net (code "101") (name "unconnected-(JP41-Pad1)") (class "Default")
      (node (ref "JP41") (pin "1") (pinfunction "1_1") (pintype "passive"))
    )
    (net (code "102") (name "unconnected-(JP41-Pad2)") (class "Default")
      (node (ref "JP41") (pin "2") (pinfunction "2_2") (pintype "passive"))
    )
    (net (code "103") (name "unconnected-(JP42-Pad1)") (class "Default")
      (node (ref "JP42") (pin "1") (pinfunction "1_1") (pintype "passive"))
    )
    (net (code "104") (name "unconnected-(JP42-Pad2)") (class "Default")
      (node (ref "JP42") (pin "2") (pinfunction "2_2") (pintype "passive"))
    )
    (net (code "105") (name "unconnected-(JP43-Pad1)") (class "Default")
      (node (ref "JP43") (pin "1") (pinfunction "1_1") (pintype "passive"))
    )
    (net (code "106") (name "unconnected-(JP43-Pad2)") (class "Default")
      (node (ref "JP43") (pin "2") (pinfunction "2_2") (pintype "passive"))
    )
    (net (code "107") (name "unconnected-(JP44-Pad1)") (class "Default")
      (node (ref "JP44") (pin "1") (pinfunction "1_1") (pintype "passive"))
    )
    (net (code "108") (name "unconnected-(JP44-Pad2)") (class "Default")
      (node (ref "JP44") (pin "2") (pinfunction "2_2") (pintype "passive"))
    )
    (net (code "109") (name "unconnected-(JP45-Pad1)") (class "Default")
      (node (ref "JP45") (pin "1") (pinfunction "1_1") (pintype "passive"))
    )
    (net (code "110") (name "unconnected-(JP45-Pad2)") (class "Default")
      (node (ref "JP45") (pin "2") (pinfunction "2_2") (pintype "passive"))
    )
    (net (code "111") (name "unconnected-(JP46-Pad1)") (class "Default")
      (node (ref "JP46") (pin "1") (pinfunction "1_1") (pintype "passive"))
    )
    (net (code "112") (name "unconnected-(JP46-Pad2)") (class "Default")
      (node (ref "JP46") (pin "2") (pinfunction "2_2") (pintype "passive"))
    )
    (net (code "113") (name "unconnected-(JP47-Pad1)") (class "Default")
      (node (ref "JP47") (pin "1") (pinfunction "1_1") (pintype "passive"))
    )
    (net (code "114") (name "unconnected-(JP47-Pad2)") (class "Default")
      (node (ref "JP47") (pin "2") (pinfunction "2_2") (pintype "passive"))
    )
    (net (code "115") (name "unconnected-(JP48-Pad1)") (class "Default")
      (node (ref "JP48") (pin "1") (pinfunction "1_1") (pintype "passive"))
    )
    (net (code "116") (name "unconnected-(JP48-Pad2)") (class "Default")
      (node (ref "JP48") (pin "2") (pinfunction "2_2") (pintype "passive"))
    )
    (net (code "117") (name "unconnected-(JP49-Pad1)") (class "Default")
      (node (ref "JP49") (pin "1") (pinfunction "1_1") (pintype "passive"))
    )
    (net (code "118") (name "unconnected-(JP49-Pad2)") (class "Default")
      (node (ref "JP49") (pin "2") (pinfunction "2_2") (pintype "passive"))
    )
    (net (code "119") (name "unconnected-(JP50-Pad1)") (class "Default")
      (node (ref "JP50") (pin "1") (pinfunction "1_1") (pintype "passive"))
    )
    (net (code "120") (name "unconnected-(JP50-Pad2)") (class "Default")
      (node (ref "JP50") (pin "2") (pinfunction "2_2") (pintype "passive"))
    )
    (net (code "121") (name "unconnected-(JP51-Pad1)") (class "Default")
      (node (ref "JP51") (pin "1") (pinfunction "1_1") (pintype "passive"))
    )
    (net (code "122") (name "unconnected-(JP51-Pad2)") (class "Default")
      (node (ref "JP51") (pin "2") (pinfunction "2_2") (pintype "passive"))
    )
    (net (code "123") (name "unconnected-(JP52-Pad1)") (class "Default")
      (node (ref "JP52") (pin "1") (pinfunction "1_1") (pintype "passive"))
    )
    (net (code "124") (name "unconnected-(JP52-Pad2)") (class "Default")
      (node (ref "JP52") (pin "2") (pinfunction "2_2") (pintype "passive"))
    )
    (net (code "125") (name "unconnected-(JP53-Pad1)") (class "Default")
      (node (ref "JP53") (pin "1") (pinfunction "1_1") (pintype "passive"))
    )
    (net (code "126") (name "unconnected-(JP53-Pad2)") (class "Default")
      (node (ref "JP53") (pin "2") (pinfunction "2_2") (pintype "passive"))
    )
    (net (code "127") (name "unconnected-(JP54-Pad1)") (class "Default")
      (node (ref "JP54") (pin "1") (pinfunction "1_1") (pintype "passive"))
    )
    (net (code "128") (name "unconnected-(JP54-Pad2)") (class "Default")
      (node (ref "JP54") (pin "2") (pinfunction "2_2") (pintype "passive"))
    )
    (net (code "129") (name "unconnected-(JP55-Pad1)") (class "Default")
      (node (ref "JP55") (pin "1") (pinfunction "1_1") (pintype "passive"))
    )
    (net (code "130") (name "unconnected-(JP55-Pad2)") (class "Default")
      (node (ref "JP55") (pin "2") (pinfunction "2_2") (pintype "passive"))
    )
    (net (code "131") (name "unconnected-(JP56-Pad1)") (class "Default")
      (node (ref "JP56") (pin "1") (pinfunction "1_1") (pintype "passive"))
    )
    (net (code "132") (name "unconnected-(JP56-Pad2)") (class "Default")
      (node (ref "JP56") (pin "2") (pinfunction "2_2") (pintype "passive"))
    )
    (net (code "133") (name "unconnected-(JP57-Pad1)") (class "Default")
      (node (ref "JP57") (pin "1") (pinfunction "1_1") (pintype "passive"))
    )
    (net (code "134") (name "unconnected-(JP57-Pad2)") (class "Default")
      (node (ref "JP57") (pin "2") (pinfunction "2_2") (pintype "passive"))
    )
    (net (code "135") (name "unconnected-(JP58-Pad1)") (class "Default")
      (node (ref "JP58") (pin "1") (pinfunction "1_1") (pintype "passive"))
    )
    (net (code "136") (name "unconnected-(JP58-Pad2)") (class "Default")
      (node (ref "JP58") (pin "2") (pinfunction "2_2") (pintype "passive"))
    )
    (net (code "137") (name "unconnected-(JP59-Pad1)") (class "Default")
      (node (ref "JP59") (pin "1") (pinfunction "1_1") (pintype "passive"))
    )
    (net (code "138") (name "unconnected-(JP59-Pad2)") (class "Default")
      (node (ref "JP59") (pin "2") (pinfunction "2_2") (pintype "passive"))
    )
    (net (code "139") (name "unconnected-(JP60-Pad1)") (class "Default")
      (node (ref "JP60") (pin "1") (pinfunction "1_1") (pintype "passive"))
    )
    (net (code "140") (name "unconnected-(JP60-Pad2)") (class "Default")
      (node (ref "JP60") (pin "2") (pinfunction "2_2") (pintype "passive"))
    )
    (net (code "141") (name "unconnected-(JP61-Pad1)") (class "Default")
      (node (ref "JP61") (pin "1") (pinfunction "1_1") (pintype "passive"))
    )
    (net (code "142") (name "unconnected-(JP61-Pad2)") (class "Default")
      (node (ref "JP61") (pin "2") (pinfunction "2_2") (pintype "passive"))
    )
    (net (code "143") (name "unconnected-(JP62-Pad1)") (class "Default")
      (node (ref "JP62") (pin "1") (pinfunction "1_1") (pintype "passive"))
    )
    (net (code "144") (name "unconnected-(JP62-Pad2)") (class "Default")
      (node (ref "JP62") (pin "2") (pinfunction "2_2") (pintype "passive"))
    )
    (net (code "145") (name "unconnected-(JP63-Pad1)") (class "Default")
      (node (ref "JP63") (pin "1") (pinfunction "1_1") (pintype "passive"))
    )
    (net (code "146") (name "unconnected-(JP63-Pad2)") (class "Default")
      (node (ref "JP63") (pin "2") (pinfunction "2_2") (pintype "passive"))
    )
    (net (code "147") (name "unconnected-(JP64-Pad1)") (class "Default")
      (node (ref "JP64") (pin "1") (pinfunction "1_1") (pintype "passive"))
    )
    (net (code "148") (name "unconnected-(JP64-Pad2)") (class "Default")
      (node (ref "JP64") (pin "2") (pinfunction "2_2") (pintype "passive"))
    )
    (net (code "149") (name "unconnected-(JP65-Pad1)") (class "Default")
      (node (ref "JP65") (pin "1") (pinfunction "1_1") (pintype "passive"))
    )
    (net (code "150") (name "unconnected-(JP65-Pad2)") (class "Default")
      (node (ref "JP65") (pin "2") (pinfunction "2_2") (pintype "passive"))
    )
    (net (code "151") (name "unconnected-(JP66-Pad1)") (class "Default")
      (node (ref "JP66") (pin "1") (pinfunction "1_1") (pintype "passive"))
    )
    (net (code "152") (name "unconnected-(JP66-Pad2)") (class "Default")
      (node (ref "JP66") (pin "2") (pinfunction "2_2") (pintype "passive"))
    )
    (net (code "153") (name "unconnected-(JP67-Pad1)") (class "Default")
      (node (ref "JP67") (pin "1") (pinfunction "1_1") (pintype "passive"))
    )
    (net (code "154") (name "unconnected-(JP67-Pad2)") (class "Default")
      (node (ref "JP67") (pin "2") (pinfunction "2_2") (pintype "passive"))
    )
    (net (code "155") (name "unconnected-(JP68-Pad1)") (class "Default")
      (node (ref "JP68") (pin "1") (pinfunction "1_1") (pintype "passive"))
    )
    (net (code "156") (name "unconnected-(JP68-Pad2)") (class "Default")
      (node (ref "JP68") (pin "2") (pinfunction "2_2") (pintype "passive"))
    )
    (net (code "157") (name "unconnected-(JP69-Pad1)") (class "Default")
      (node (ref "JP69") (pin "1") (pinfunction "1_1") (pintype "passive"))
    )
    (net (code "158") (name "unconnected-(JP69-Pad2)") (class "Default")
      (node (ref "JP69") (pin "2") (pinfunction "2_2") (pintype "passive"))
    )
    (net (code "159") (name "unconnected-(JP70-Pad1)") (class "Default")
      (node (ref "JP70") (pin "1") (pinfunction "1_1") (pintype "passive"))
    )
    (net (code "160") (name "unconnected-(JP70-Pad2)") (class "Default")
      (node (ref "JP70") (pin "2") (pinfunction "2_2") (pintype "passive"))
    )
    (net (code "161") (name "unconnected-(JP71-Pad1)") (class "Default")
      (node (ref "JP71") (pin "1") (pinfunction "1_1") (pintype "passive"))
    )
    (net (code "162") (name "unconnected-(JP71-Pad2)") (class "Default")
      (node (ref "JP71") (pin "2") (pinfunction "2_2") (pintype "passive"))
    )
    (net (code "163") (name "unconnected-(JP72-Pad1)") (class "Default")
      (node (ref "JP72") (pin "1") (pinfunction "1_1") (pintype "passive"))
    )
    (net (code "164") (name "unconnected-(JP72-Pad2)") (class "Default")
      (node (ref "JP72") (pin "2") (pinfunction "2_2") (pintype "passive"))
    )
    (net (code "165") (name "unconnected-(JP73-Pad1)") (class "Default")
      (node (ref "JP73") (pin "1") (pinfunction "1_1") (pintype "passive"))
    )
    (net (code "166") (name "unconnected-(JP73-Pad2)") (class "Default")
      (node (ref "JP73") (pin "2") (pinfunction "2_2") (pintype "passive"))
    )
    (net (code "167") (name "unconnected-(JP74-Pad1)") (class "Default")
      (node (ref "JP74") (pin "1") (pinfunction "1_1") (pintype "passive"))
    )
    (net (code "168") (name "unconnected-(JP74-Pad2)") (class "Default")
      (node (ref "JP74") (pin "2") (pinfunction "2_2") (pintype "passive"))
    )
    (net (code "169") (name "unconnected-(JP75-Pad1)") (class "Default")
      (node (ref "JP75") (pin "1") (pinfunction "1_1") (pintype "passive"))
    )
    (net (code "170") (name "unconnected-(JP75-Pad2)") (class "Default")
      (node (ref "JP75") (pin "2") (pinfunction "2_2") (pintype "passive"))
    )
    (net (code "171") (name "unconnected-(JP76-Pad1)") (class "Default")
      (node (ref "JP76") (pin "1") (pinfunction "1_1") (pintype "passive"))
    )
    (net (code "172") (name "unconnected-(JP76-Pad2)") (class "Default")
      (node (ref "JP76") (pin "2") (pinfunction "2_2") (pintype "passive"))
    )
    (net (code "173") (name "unconnected-(JP77-Pad1)") (class "Default")
      (node (ref "JP77") (pin "1") (pinfunction "1_1") (pintype "passive"))
    )
    (net (code "174") (name "unconnected-(JP77-Pad2)") (class "Default")
      (node (ref "JP77") (pin "2") (pinfunction "2_2") (pintype "passive"))
    )
    (net (code "175") (name "unconnected-(JP78-Pad1)") (class "Default")
      (node (ref "JP78") (pin "1") (pinfunction "1_1") (pintype "passive"))
    )
    (net (code "176") (name "unconnected-(JP78-Pad2)") (class "Default")
      (node (ref "JP78") (pin "2") (pinfunction "2_2") (pintype "passive"))
    )
    (net (code "177") (name "unconnected-(JP79-Pad1)") (class "Default")
      (node (ref "JP79") (pin "1") (pinfunction "1_1") (pintype "passive"))
    )
    (net (code "178") (name "unconnected-(JP79-Pad2)") (class "Default")
      (node (ref "JP79") (pin "2") (pinfunction "2_2") (pintype "passive"))
    )
    (net (code "179") (name "unconnected-(JP80-Pad1)") (class "Default")
      (node (ref "JP80") (pin "1") (pinfunction "1_1") (pintype "passive"))
    )
    (net (code "180") (name "unconnected-(JP80-Pad2)") (class "Default")
      (node (ref "JP80") (pin "2") (pinfunction "2_2") (pintype "passive"))
    )
    (net (code "181") (name "unconnected-(JP81-Pad1)") (class "Default")
      (node (ref "JP81") (pin "1") (pinfunction "1_1") (pintype "passive"))
    )
    (net (code "182") (name "unconnected-(JP81-Pad2)") (class "Default")
      (node (ref "JP81") (pin "2") (pinfunction "2_2") (pintype "passive"))
    )
    (net (code "183") (name "unconnected-(JP82-Pad1)") (class "Default")
      (node (ref "JP82") (pin "1") (pinfunction "1_1") (pintype "passive"))
    )
    (net (code "184") (name "unconnected-(JP82-Pad2)") (class "Default")
      (node (ref "JP82") (pin "2") (pinfunction "2_2") (pintype "passive"))
    )
    (net (code "185") (name "unconnected-(JP83-Pad1)") (class "Default")
      (node (ref "JP83") (pin "1") (pinfunction "1_1") (pintype "passive"))
    )
    (net (code "186") (name "unconnected-(JP83-Pad2)") (class "Default")
      (node (ref "JP83") (pin "2") (pinfunction "2_2") (pintype "passive"))
    )
    (net (code "187") (name "unconnected-(JP84-Pad1)") (class "Default")
      (node (ref "JP84") (pin "1") (pinfunction "1_1") (pintype "passive"))
    )
    (net (code "188") (name "unconnected-(JP84-Pad2)") (class "Default")
      (node (ref "JP84") (pin "2") (pinfunction "2_2") (pintype "passive"))
    )
  )
)
